# esp12_Epaper4_2.net
KiCad netlist of a schematic drawn in EAGLE
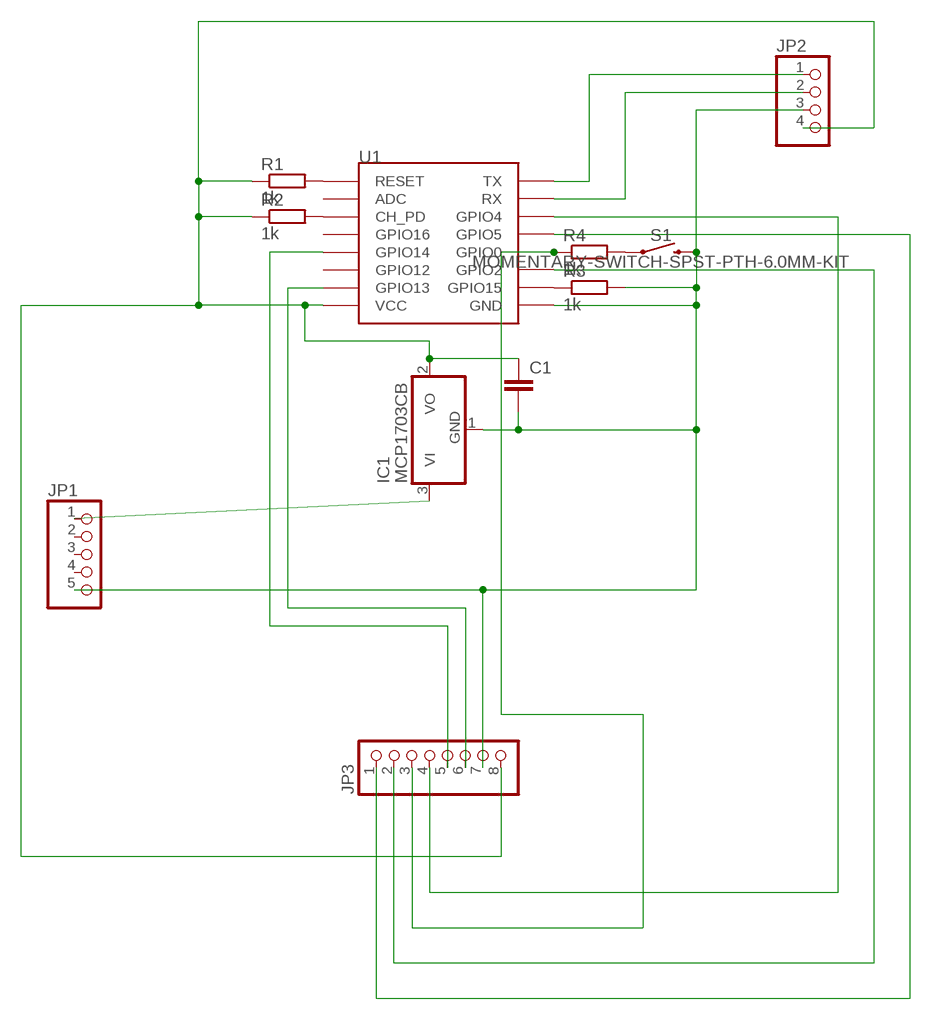
[diagram p0: schematic, sheet 1]

(export (version "E")
  (design (tool "Eeschema 10.0.6"))
  (components
    (comp (ref "C1")
      (value "C-EU025-050X050")
      (footprint "eagle-import:C025-050X050")
      (libsource (lib "eagle-import") (part "C-EU025-050X050"))
    )
    (comp (ref "IC1")
      (value "MCP1703CB")
      (footprint "eagle-import:SOT23")
      (libsource (lib "eagle-import") (part "MCP1703CB"))
    )
    (comp (ref "JP1")
      (value "PINHD-1X5")
      (footprint "eagle-import:1X05")
      (libsource (lib "eagle-import") (part "PINHD-1X5"))
    )
    (comp (ref "JP2")
      (value "PINHD-1X4/90")
      (footprint "eagle-import:1X04_90")
      (libsource (lib "eagle-import") (part "PINHD-1X4/90"))
    )
    (comp (ref "JP3")
      (value "PINHD-1X8/90")
      (footprint "eagle-import:1X08_90")
      (libsource (lib "eagle-import") (part "PINHD-1X8/90"))
    )
    (comp (ref "R1")
      (value "1k")
      (footprint "eagle-import:R1206")
      (libsource (lib "eagle-import") (part "R-EU_R1206"))
    )
    (comp (ref "R2")
      (value "1k")
      (footprint "eagle-import:R1206")
      (libsource (lib "eagle-import") (part "R-EU_R1206"))
    )
    (comp (ref "R3")
      (value "1k")
      (footprint "eagle-import:R1206")
      (libsource (lib "eagle-import") (part "R-EU_R1206"))
    )
    (comp (ref "R4")
      (value "1k")
      (footprint "eagle-import:R1206")
      (libsource (lib "eagle-import") (part "R-EU_R1206"))
    )
    (comp (ref "S1")
      (value "MOMENTARY-SWITCH-SPST-PTH-6.0MM-KIT")
      (footprint "eagle-import:TACTILE_SWITCH_PTH_6.0MM_KIT")
      (libsource (lib "eagle-import") (part "MOMENTARY-SWITCH-SPST-PTH-6.0MM-KIT"))
    )
    (comp (ref "U1")
      (value "ESP12")
      (footprint "eagle-import:ESP12")
      (libsource (lib "eagle-import") (part "ESP12"))
    )
  )
  (nets
    (net (code "1") (name "Net-(IC1-GND)") (class "Default")
      (node (ref "C1") (pin "2") (pinfunction "2_2") (pintype "passive"))
      (node (ref "IC1") (pin "1") (pinfunction "GND_1") (pintype "passive"))
      (node (ref "JP1") (pin "5") (pinfunction "5_5") (pintype "passive"))
      (node (ref "JP2") (pin "3") (pinfunction "3_3") (pintype "passive"))
      (node (ref "JP3") (pin "7") (pinfunction "7_7") (pintype "passive"))
      (node (ref "R3") (pin "2") (pinfunction "2_2") (pintype "passive"))
      (node (ref "S1") (pin "3") (pinfunction "2_3") (pintype "passive"))
      (node (ref "U1") (pin "GND") (pinfunction "GND_GND") (pintype "bidirectional"))
    )
    (net (code "2") (name "Net-(IC1-VI)") (class "Default")
      (node (ref "IC1") (pin "3") (pinfunction "VI_3") (pintype "input"))
      (node (ref "JP1") (pin "1") (pinfunction "1_1") (pintype "passive"))
    )
    (net (code "3") (name "Net-(IC1-VO)") (class "Default")
      (node (ref "C1") (pin "1") (pinfunction "1_1") (pintype "passive"))
      (node (ref "IC1") (pin "2") (pinfunction "VO_2") (pintype "passive"))
      (node (ref "JP2") (pin "4") (pinfunction "4_4") (pintype "passive"))
      (node (ref "JP3") (pin "8") (pinfunction "8_8") (pintype "passive"))
      (node (ref "R1") (pin "1") (pinfunction "1_1") (pintype "passive"))
      (node (ref "R2") (pin "1") (pinfunction "1_1") (pintype "passive"))
      (node (ref "U1") (pin "VCC") (pinfunction "VCC_VCC") (pintype "bidirectional"))
    )
    (net (code "4") (name "Net-(JP2-Pad1)") (class "Default")
      (node (ref "JP2") (pin "1") (pinfunction "1_1") (pintype "passive"))
      (node (ref "U1") (pin "TX") (pinfunction "TX_TX") (pintype "bidirectional"))
    )
    (net (code "5") (name "Net-(JP2-Pad2)") (class "Default")
      (node (ref "JP2") (pin "2") (pinfunction "2_2") (pintype "passive"))
      (node (ref "U1") (pin "RX") (pinfunction "RX_RX") (pintype "bidirectional"))
    )
    (net (code "6") (name "Net-(JP3-Pad1)") (class "Default")
      (node (ref "JP3") (pin "1") (pinfunction "1_1") (pintype "passive"))
      (node (ref "U1") (pin "GPIO5") (pinfunction "GPIO5_GPIO5") (pintype "bidirectional"))
    )
    (net (code "7") (name "Net-(JP3-Pad2)") (class "Default")
      (node (ref "JP3") (pin "2") (pinfunction "2_2") (pintype "passive"))
      (node (ref "U1") (pin "GPIO2") (pinfunction "GPIO2_GPIO2") (pintype "bidirectional"))
    )
    (net (code "8") (name "Net-(JP3-Pad3)") (class "Default")
      (node (ref "JP3") (pin "3") (pinfunction "3_3") (pintype "passive"))
      (node (ref "R4") (pin "1") (pinfunction "1_1") (pintype "passive"))
      (node (ref "U1") (pin "GPIO0") (pinfunction "GPIO0_GPIO0") (pintype "bidirectional"))
    )
    (net (code "9") (name "Net-(JP3-Pad4)") (class "Default")
      (node (ref "JP3") (pin "4") (pinfunction "4_4") (pintype "passive"))
      (node (ref "U1") (pin "GPIO4") (pinfunction "GPIO4_GPIO4") (pintype "bidirectional"))
    )
    (net (code "10") (name "Net-(JP3-Pad5)") (class "Default")
      (node (ref "JP3") (pin "5") (pinfunction "5_5") (pintype "passive"))
      (node (ref "U1") (pin "GPIO14") (pinfunction "GPIO14_GPIO14") (pintype "bidirectional"))
    )
    (net (code "11") (name "Net-(JP3-Pad6)") (class "Default")
      (node (ref "JP3") (pin "6") (pinfunction "6_6") (pintype "passive"))
      (node (ref "U1") (pin "GPIO13") (pinfunction "GPIO13_GPIO13") (pintype "bidirectional"))
    )
    (net (code "12") (name "Net-(R1-Pad2)") (class "Default")
      (node (ref "R1") (pin "2") (pinfunction "2_2") (pintype "passive"))
      (node (ref "U1") (pin "RESET") (pinfunction "RESET_RESET") (pintype "bidirectional"))
    )
    (net (code "13") (name "Net-(R2-Pad2)") (class "Default")
      (node (ref "R2") (pin "2") (pinfunction "2_2") (pintype "passive"))
      (node (ref "U1") (pin "CH_PD") (pinfunction "CH_PD_CH_PD") (pintype "bidirectional"))
    )
    (net (code "14") (name "Net-(R3-Pad1)") (class "Default")
      (node (ref "R3") (pin "1") (pinfunction "1_1") (pintype "passive"))
      (node (ref "U1") (pin "GPIO15") (pinfunction "GPIO15_GPIO15") (pintype "bidirectional"))
    )
    (net (code "15") (name "Net-(R4-Pad2)") (class "Default")
      (node (ref "R4") (pin "2") (pinfunction "2_2") (pintype "passive"))
      (node (ref "S1") (pin "1") (pinfunction "1_1") (pintype "passive"))
    )
    (net (code "16") (name "unconnected-(JP1-Pad2)") (class "Default")
      (node (ref "JP1") (pin "2") (pinfunction "2_2") (pintype "passive"))
    )
    (net (code "17") (name "unconnected-(JP1-Pad3)") (class "Default")
      (node (ref "JP1") (pin "3") (pinfunction "3_3") (pintype "passive"))
    )
    (net (code "18") (name "unconnected-(JP1-Pad4)") (class "Default")
      (node (ref "JP1") (pin "4") (pinfunction "4_4") (pintype "passive"))
    )
    (net (code "19") (name "unconnected-(U1-PadADC)") (class "Default")
      (node (ref "U1") (pin "ADC") (pinfunction "ADC_ADC") (pintype "bidirectional"))
    )
    (net (code "20") (name "unconnected-(U1-PadGPIO12)") (class "Default")
      (node (ref "U1") (pin "GPIO12") (pinfunction "GPIO12_GPIO12") (pintype "bidirectional"))
    )
    (net (code "21") (name "unconnected-(U1-PadGPIO16)") (class "Default")
      (node (ref "U1") (pin "GPIO16") (pinfunction "GPIO16_GPIO16") (pintype "bidirectional"))
    )
  )
)
